# T35_5_MIPI.net
KiCad netlist of a schematic drawn in Altium Designer
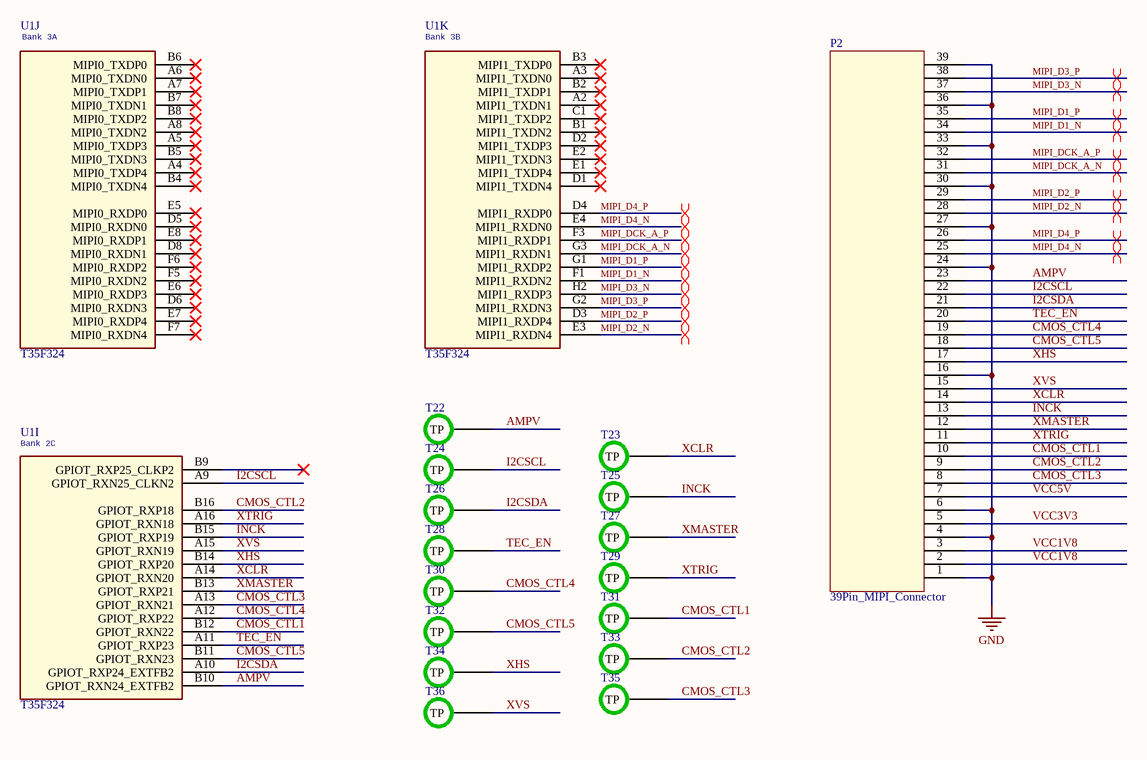
[diagram p0: T35_5_MIPI.SchDoc]

(export (version "E")
  (design (tool "Eeschema 10.0.6"))
  (components
    (comp (ref "P2")
      (value "39Pin_MIPI_Connector")
      (footprint "39pin_0.3错位排序")
      (description "0.3mm间距39PinFPC插座")
      (libsource (lib "T35-V2") (part "39Pin_MIPI_Connector"))
    )
    (comp (ref "T22")
      (value "~")
      (footprint "TP-S")
      (description "测试点")
      (libsource (lib "QHY_SCHLIB") (part "TP"))
    )
    (comp (ref "T23")
      (value "~")
      (footprint "TP-S")
      (description "测试点")
      (libsource (lib "QHY_SCHLIB") (part "TP"))
    )
    (comp (ref "T24")
      (value "~")
      (footprint "TP-S")
      (description "测试点")
      (libsource (lib "QHY_SCHLIB") (part "TP"))
    )
    (comp (ref "T25")
      (value "~")
      (footprint "TP-S")
      (description "测试点")
      (libsource (lib "QHY_SCHLIB") (part "TP"))
    )
    (comp (ref "T26")
      (value "~")
      (footprint "TP-S")
      (description "测试点")
      (libsource (lib "QHY_SCHLIB") (part "TP"))
    )
    (comp (ref "T27")
      (value "~")
      (footprint "TP-S")
      (description "测试点")
      (libsource (lib "QHY_SCHLIB") (part "TP"))
    )
    (comp (ref "T28")
      (value "~")
      (footprint "TP-S")
      (description "测试点")
      (libsource (lib "QHY_SCHLIB") (part "TP"))
    )
    (comp (ref "T29")
      (value "~")
      (footprint "TP-S")
      (description "测试点")
      (libsource (lib "QHY_SCHLIB") (part "TP"))
    )
    (comp (ref "T30")
      (value "~")
      (footprint "TP-S")
      (description "测试点")
      (libsource (lib "QHY_SCHLIB") (part "TP"))
    )
    (comp (ref "T31")
      (value "~")
      (footprint "TP-S")
      (description "测试点")
      (libsource (lib "QHY_SCHLIB") (part "TP"))
    )
    (comp (ref "T32")
      (value "~")
      (footprint "TP-S")
      (description "测试点")
      (libsource (lib "QHY_SCHLIB") (part "TP"))
    )
    (comp (ref "T33")
      (value "~")
      (footprint "TP-S")
      (description "测试点")
      (libsource (lib "QHY_SCHLIB") (part "TP"))
    )
    (comp (ref "T34")
      (value "~")
      (footprint "TP-S")
      (description "测试点")
      (libsource (lib "QHY_SCHLIB") (part "TP"))
    )
    (comp (ref "T35")
      (value "~")
      (footprint "TP-S")
      (description "测试点")
      (libsource (lib "QHY_SCHLIB") (part "TP"))
    )
    (comp (ref "T36")
      (value "~")
      (footprint "TP-S")
      (description "测试点")
      (libsource (lib "QHY_SCHLIB") (part "TP"))
    )
    (comp (ref "U1")
      (value "T35F324")
      (footprint "T35-F324-BGA100P9X9-81A")
      (description "FPGA芯片")
      (libsource (lib "orcadt35-v1.0_Library") (part "T35F324"))
    )
  )
  (nets
    (net (code "1") (name "/AMPV") (class "Default")
      (node (ref "P2") (pin "23") (pintype "passive"))
      (node (ref "T22") (pin "1") (pinfunction "TP_1") (pintype "passive"))
      (node (ref "U1") (pin "B10") (pinfunction "GPIOT_RXN24_EXTFB2_B10") (pintype "passive"))
    )
    (net (code "2") (name "/CMOS_CTL1") (class "Default")
      (node (ref "P2") (pin "10") (pintype "passive"))
      (node (ref "T31") (pin "1") (pinfunction "TP_1") (pintype "passive"))
      (node (ref "U1") (pin "B12") (pinfunction "GPIOT_RXN22_B12") (pintype "passive"))
    )
    (net (code "3") (name "/CMOS_CTL2") (class "Default")
      (node (ref "P2") (pin "9") (pintype "passive"))
      (node (ref "T33") (pin "1") (pinfunction "TP_1") (pintype "passive"))
      (node (ref "U1") (pin "B16") (pinfunction "GPIOT_RXP18_B16") (pintype "passive"))
    )
    (net (code "4") (name "/CMOS_CTL3") (class "Default")
      (node (ref "P2") (pin "8") (pintype "passive"))
      (node (ref "T35") (pin "1") (pinfunction "TP_1") (pintype "passive"))
      (node (ref "U1") (pin "A13") (pinfunction "GPIOT_RXN21_A13") (pintype "passive"))
    )
    (net (code "5") (name "/CMOS_CTL4") (class "Default")
      (node (ref "P2") (pin "19") (pintype "passive"))
      (node (ref "T30") (pin "1") (pinfunction "TP_1") (pintype "passive"))
      (node (ref "U1") (pin "A12") (pinfunction "GPIOT_RXP22_A12") (pintype "passive"))
    )
    (net (code "6") (name "/CMOS_CTL5") (class "Default")
      (node (ref "P2") (pin "18") (pintype "passive"))
      (node (ref "T32") (pin "1") (pinfunction "TP_1") (pintype "passive"))
      (node (ref "U1") (pin "B11") (pinfunction "GPIOT_RXN23_B11") (pintype "passive"))
    )
    (net (code "7") (name "/I2CSCL") (class "Default")
      (node (ref "P2") (pin "22") (pintype "passive"))
      (node (ref "T24") (pin "1") (pinfunction "TP_1") (pintype "passive"))
      (node (ref "U1") (pin "A9") (pinfunction "GPIOT_RXN25_CLKN2_A9") (pintype "passive"))
    )
    (net (code "8") (name "/I2CSDA") (class "Default")
      (node (ref "P2") (pin "21") (pintype "passive"))
      (node (ref "T26") (pin "1") (pinfunction "TP_1") (pintype "passive"))
      (node (ref "U1") (pin "A10") (pinfunction "GPIOT_RXP24_EXTFB2_A10") (pintype "passive"))
    )
    (net (code "9") (name "/INCK") (class "Default")
      (node (ref "P2") (pin "13") (pintype "passive"))
      (node (ref "T25") (pin "1") (pinfunction "TP_1") (pintype "passive"))
      (node (ref "U1") (pin "B15") (pinfunction "GPIOT_RXP19_B15") (pintype "passive"))
    )
    (net (code "10") (name "/MIPI_D1_N") (class "Default")
      (node (ref "P2") (pin "34") (pinfunction "34_34") (pintype "passive"))
      (node (ref "U1") (pin "F1") (pinfunction "MIPI1_RXDN2_F1") (pintype "passive"))
    )
    (net (code "11") (name "/MIPI_D1_P") (class "Default")
      (node (ref "P2") (pin "35") (pinfunction "35_35") (pintype "passive"))
      (node (ref "U1") (pin "G1") (pinfunction "MIPI1_RXDP2_G1") (pintype "passive"))
    )
    (net (code "12") (name "/MIPI_D2_N") (class "Default")
      (node (ref "P2") (pin "28") (pintype "passive"))
      (node (ref "U1") (pin "E3") (pinfunction "MIPI1_RXDN4_E3") (pintype "passive"))
    )
    (net (code "13") (name "/MIPI_D2_P") (class "Default")
      (node (ref "P2") (pin "29") (pintype "passive"))
      (node (ref "U1") (pin "D3") (pinfunction "MIPI1_RXDP4_D3") (pintype "passive"))
    )
    (net (code "14") (name "/MIPI_D3_N") (class "Default")
      (node (ref "P2") (pin "37") (pinfunction "37_37") (pintype "passive"))
      (node (ref "U1") (pin "H2") (pinfunction "MIPI1_RXDP3_H2") (pintype "passive"))
    )
    (net (code "15") (name "/MIPI_D3_P") (class "Default")
      (node (ref "P2") (pin "38") (pinfunction "38_38") (pintype "passive"))
      (node (ref "U1") (pin "G2") (pinfunction "MIPI1_RXDN3_G2") (pintype "passive"))
    )
    (net (code "16") (name "/MIPI_D4_N") (class "Default")
      (node (ref "P2") (pin "25") (pintype "passive"))
      (node (ref "U1") (pin "E4") (pinfunction "MIPI1_RXDN0_E4") (pintype "passive"))
    )
    (net (code "17") (name "/MIPI_D4_P") (class "Default")
      (node (ref "P2") (pin "26") (pintype "passive"))
      (node (ref "U1") (pin "D4") (pinfunction "MIPI1_RXDP0_D4") (pintype "passive"))
    )
    (net (code "18") (name "/MIPI_DCK_A_N") (class "Default")
      (node (ref "P2") (pin "31") (pintype "passive"))
      (node (ref "U1") (pin "G3") (pinfunction "MIPI1_RXDN1_G3") (pintype "passive"))
    )
    (net (code "19") (name "/MIPI_DCK_A_P") (class "Default")
      (node (ref "P2") (pin "32") (pinfunction "32_32") (pintype "passive"))
      (node (ref "U1") (pin "F3") (pinfunction "MIPI1_RXDP1_F3") (pintype "passive"))
    )
    (net (code "20") (name "/TEC_EN") (class "Default")
      (node (ref "P2") (pin "20") (pintype "passive"))
      (node (ref "T28") (pin "1") (pinfunction "TP_1") (pintype "passive"))
      (node (ref "U1") (pin "A11") (pinfunction "GPIOT_RXP23_A11") (pintype "passive"))
    )
    (net (code "21") (name "/VCC1V8") (class "Default")
      (node (ref "P2") (pin "2") (pintype "passive"))
      (node (ref "P2") (pin "3") (pintype "passive"))
    )
    (net (code "22") (name "/VCC3V3") (class "Default") (node (ref "P2") (pin "5") (pintype "passive")))
    (net (code "23") (name "/VCC5V") (class "Default") (node (ref "P2") (pin "7") (pintype "passive")))
    (net (code "24") (name "/XCLR") (class "Default")
      (node (ref "P2") (pin "14") (pintype "passive"))
      (node (ref "T23") (pin "1") (pinfunction "TP_1") (pintype "passive"))
      (node (ref "U1") (pin "A14") (pinfunction "GPIOT_RXN20_A14") (pintype "passive"))
    )
    (net (code "25") (name "/XHS") (class "Default")
      (node (ref "P2") (pin "17") (pintype "passive"))
      (node (ref "T34") (pin "1") (pinfunction "TP_1") (pintype "passive"))
      (node (ref "U1") (pin "B14") (pinfunction "GPIOT_RXP20_B14") (pintype "passive"))
    )
    (net (code "26") (name "/XMASTER") (class "Default")
      (node (ref "P2") (pin "12") (pintype "passive"))
      (node (ref "T27") (pin "1") (pinfunction "TP_1") (pintype "passive"))
      (node (ref "U1") (pin "B13") (pinfunction "GPIOT_RXP21_B13") (pintype "passive"))
    )
    (net (code "27") (name "/XTRIG") (class "Default")
      (node (ref "P2") (pin "11") (pintype "passive"))
      (node (ref "T29") (pin "1") (pinfunction "TP_1") (pintype "passive"))
      (node (ref "U1") (pin "A16") (pinfunction "GPIOT_RXN18_A16") (pintype "passive"))
    )
    (net (code "28") (name "/XVS") (class "Default")
      (node (ref "P2") (pin "15") (pintype "passive"))
      (node (ref "T36") (pin "1") (pinfunction "TP_1") (pintype "passive"))
      (node (ref "U1") (pin "A15") (pinfunction "GPIOT_RXN19_A15") (pintype "passive"))
    )
    (net (code "29") (name "GND") (class "Default")
      (node (ref "P2") (pin "1") (pintype "passive"))
      (node (ref "P2") (pin "16") (pintype "passive"))
      (node (ref "P2") (pin "24") (pintype "passive"))
      (node (ref "P2") (pin "27") (pintype "passive"))
      (node (ref "P2") (pin "30") (pintype "passive"))
      (node (ref "P2") (pin "33") (pinfunction "33_33") (pintype "passive"))
      (node (ref "P2") (pin "36") (pinfunction "36_36") (pintype "passive"))
      (node (ref "P2") (pin "39") (pinfunction "39_39") (pintype "passive"))
      (node (ref "P2") (pin "4") (pintype "passive"))
      (node (ref "P2") (pin "6") (pintype "passive"))
    )
    (net (code "30") (name "unconnected-(U1I-GPIOT_RXP25_CLKP2-PadB9)") (class "Default")
      (node (ref "U1") (pin "B9") (pinfunction "GPIOT_RXP25_CLKP2_B9") (pintype "passive+no_connect"))
    )
    (net (code "31") (name "unconnected-(U1J-MIPI0_RXDN0-PadD5)") (class "Default")
      (node (ref "U1") (pin "D5") (pinfunction "MIPI0_RXDN0_D5") (pintype "passive+no_connect"))
    )
    (net (code "32") (name "unconnected-(U1J-MIPI0_RXDN1-PadD8)") (class "Default")
      (node (ref "U1") (pin "D8") (pinfunction "MIPI0_RXDN1_D8") (pintype "passive+no_connect"))
    )
    (net (code "33") (name "unconnected-(U1J-MIPI0_RXDN2-PadF5)") (class "Default")
      (node (ref "U1") (pin "F5") (pinfunction "MIPI0_RXDN2_F5") (pintype "passive+no_connect"))
    )
    (net (code "34") (name "unconnected-(U1J-MIPI0_RXDN3-PadD6)") (class "Default")
      (node (ref "U1") (pin "D6") (pinfunction "MIPI0_RXDN3_D6") (pintype "passive+no_connect"))
    )
    (net (code "35") (name "unconnected-(U1J-MIPI0_RXDN4-PadF7)") (class "Default")
      (node (ref "U1") (pin "F7") (pinfunction "MIPI0_RXDN4_F7") (pintype "passive+no_connect"))
    )
    (net (code "36") (name "unconnected-(U1J-MIPI0_RXDP0-PadE5)") (class "Default")
      (node (ref "U1") (pin "E5") (pinfunction "MIPI0_RXDP0_E5") (pintype "passive+no_connect"))
    )
    (net (code "37") (name "unconnected-(U1J-MIPI0_RXDP1-PadE8)") (class "Default")
      (node (ref "U1") (pin "E8") (pinfunction "MIPI0_RXDP1_E8") (pintype "passive+no_connect"))
    )
    (net (code "38") (name "unconnected-(U1J-MIPI0_RXDP2-PadF6)") (class "Default")
      (node (ref "U1") (pin "F6") (pinfunction "MIPI0_RXDP2_F6") (pintype "passive+no_connect"))
    )
    (net (code "39") (name "unconnected-(U1J-MIPI0_RXDP3-PadE6)") (class "Default")
      (node (ref "U1") (pin "E6") (pinfunction "MIPI0_RXDP3_E6") (pintype "passive+no_connect"))
    )
    (net (code "40") (name "unconnected-(U1J-MIPI0_RXDP4-PadE7)") (class "Default")
      (node (ref "U1") (pin "E7") (pinfunction "MIPI0_RXDP4_E7") (pintype "passive+no_connect"))
    )
    (net (code "41") (name "unconnected-(U1J-MIPI0_TXDN0-PadA6)") (class "Default")
      (node (ref "U1") (pin "A6") (pinfunction "MIPI0_TXDN0_A6") (pintype "passive+no_connect"))
    )
    (net (code "42") (name "unconnected-(U1J-MIPI0_TXDN1-PadB7)") (class "Default")
      (node (ref "U1") (pin "B7") (pinfunction "MIPI0_TXDN1_B7") (pintype "passive+no_connect"))
    )
    (net (code "43") (name "unconnected-(U1J-MIPI0_TXDN2-PadA8)") (class "Default")
      (node (ref "U1") (pin "A8") (pinfunction "MIPI0_TXDN2_A8") (pintype "passive+no_connect"))
    )
    (net (code "44") (name "unconnected-(U1J-MIPI0_TXDN3-PadB5)") (class "Default")
      (node (ref "U1") (pin "B5") (pinfunction "MIPI0_TXDN3_B5") (pintype "passive+no_connect"))
    )
    (net (code "45") (name "unconnected-(U1J-MIPI0_TXDN4-PadB4)") (class "Default")
      (node (ref "U1") (pin "B4") (pinfunction "MIPI0_TXDN4_B4") (pintype "passive+no_connect"))
    )
    (net (code "46") (name "unconnected-(U1J-MIPI0_TXDP0-PadB6)") (class "Default")
      (node (ref "U1") (pin "B6") (pinfunction "MIPI0_TXDP0_B6") (pintype "passive+no_connect"))
    )
    (net (code "47") (name "unconnected-(U1J-MIPI0_TXDP1-PadA7)") (class "Default")
      (node (ref "U1") (pin "A7") (pinfunction "MIPI0_TXDP1_A7") (pintype "passive+no_connect"))
    )
    (net (code "48") (name "unconnected-(U1J-MIPI0_TXDP2-PadB8)") (class "Default")
      (node (ref "U1") (pin "B8") (pinfunction "MIPI0_TXDP2_B8") (pintype "passive+no_connect"))
    )
    (net (code "49") (name "unconnected-(U1J-MIPI0_TXDP3-PadA5)") (class "Default")
      (node (ref "U1") (pin "A5") (pinfunction "MIPI0_TXDP3_A5") (pintype "passive+no_connect"))
    )
    (net (code "50") (name "unconnected-(U1J-MIPI0_TXDP4-PadA4)") (class "Default")
      (node (ref "U1") (pin "A4") (pinfunction "MIPI0_TXDP4_A4") (pintype "passive+no_connect"))
    )
    (net (code "51") (name "unconnected-(U1K-MIPI1_TXDN0-PadA3)") (class "Default")
      (node (ref "U1") (pin "A3") (pinfunction "MIPI1_TXDN0_A3") (pintype "passive+no_connect"))
    )
    (net (code "52") (name "unconnected-(U1K-MIPI1_TXDN1-PadA2)") (class "Default")
      (node (ref "U1") (pin "A2") (pinfunction "MIPI1_TXDN1_A2") (pintype "passive+no_connect"))
    )
    (net (code "53") (name "unconnected-(U1K-MIPI1_TXDN2-PadB1)") (class "Default")
      (node (ref "U1") (pin "B1") (pinfunction "MIPI1_TXDN2_B1") (pintype "passive+no_connect"))
    )
    (net (code "54") (name "unconnected-(U1K-MIPI1_TXDN3-PadE2)") (class "Default")
      (node (ref "U1") (pin "E2") (pinfunction "MIPI1_TXDN3_E2") (pintype "passive+no_connect"))
    )
    (net (code "55") (name "unconnected-(U1K-MIPI1_TXDN4-PadD1)") (class "Default")
      (node (ref "U1") (pin "D1") (pinfunction "MIPI1_TXDN4_D1") (pintype "passive+no_connect"))
    )
    (net (code "56") (name "unconnected-(U1K-MIPI1_TXDP0-PadB3)") (class "Default")
      (node (ref "U1") (pin "B3") (pinfunction "MIPI1_TXDP0_B3") (pintype "passive+no_connect"))
    )
    (net (code "57") (name "unconnected-(U1K-MIPI1_TXDP1-PadB2)") (class "Default")
      (node (ref "U1") (pin "B2") (pinfunction "MIPI1_TXDP1_B2") (pintype "passive+no_connect"))
    )
    (net (code "58") (name "unconnected-(U1K-MIPI1_TXDP2-PadC1)") (class "Default")
      (node (ref "U1") (pin "C1") (pinfunction "MIPI1_TXDP2_C1") (pintype "passive+no_connect"))
    )
    (net (code "59") (name "unconnected-(U1K-MIPI1_TXDP3-PadD2)") (class "Default")
      (node (ref "U1") (pin "D2") (pinfunction "MIPI1_TXDP3_D2") (pintype "passive+no_connect"))
    )
    (net (code "60") (name "unconnected-(U1K-MIPI1_TXDP4-PadE1)") (class "Default")
      (node (ref "U1") (pin "E1") (pinfunction "MIPI1_TXDP4_E1") (pintype "passive+no_connect"))
    )
  )
)
